# ic.net
KiCad netlist of a schematic drawn in Altium Designer
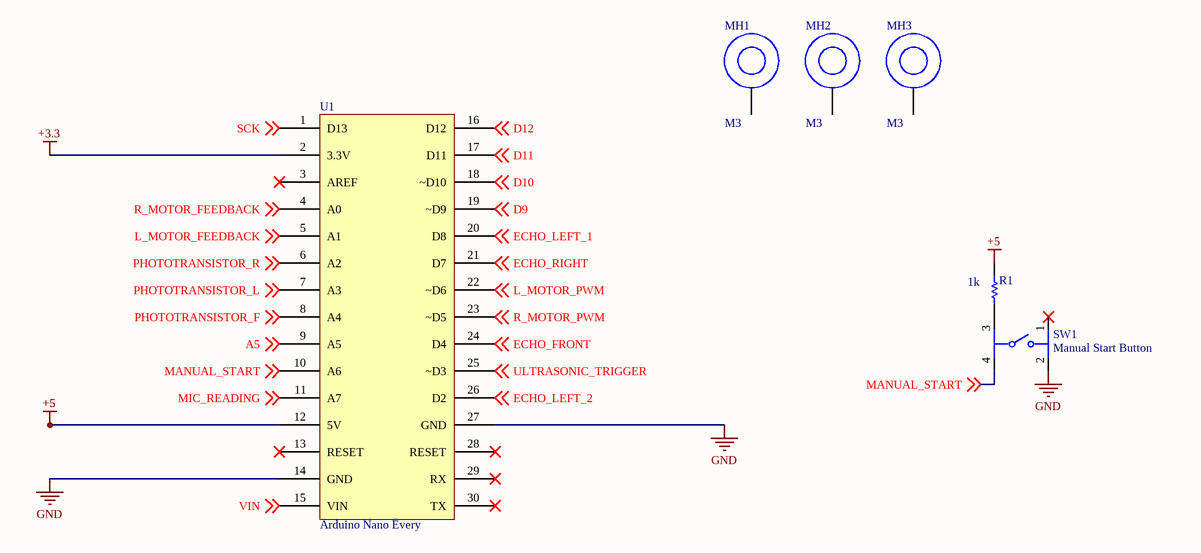
[diagram p0: ic.SchDoc]

(export (version "E")
  (design (tool "Eeschema 10.0.6"))
  (components
    (comp (ref "MH1")
      (value "M3")
      (footprint "PTH_M3")
      (description "M3 Plated Through Hole")
      (libsource (lib "Schlib1") (part "PTH"))
    )
    (comp (ref "MH2")
      (value "M3")
      (footprint "PTH_M3")
      (description "M3 Plated Through Hole")
      (libsource (lib "Schlib1") (part "PTH"))
    )
    (comp (ref "MH3")
      (value "M3")
      (footprint "PTH_M3")
      (description "M3 Plated Through Hole")
      (libsource (lib "Schlib1") (part "PTH"))
    )
    (comp (ref "R1")
      (value "1k")
      (footprint "RESC2013X50X30NL20T20")
      (fields (field (name "PART NUMBER") "CRCW08051K00FKEA") (field (name "MANUFACTURER") "Vishay Dale"))
      (libsource (lib "Altium Content Vault") (part "RES"))
    )
    (comp (ref "SW1")
      (value "Manual Start Button")
      (footprint "FP-PTS645SM43SMTR92LFS-MFG")
      (description "SWITCH TACTILE SPST-NO 0.05A 12V")
      (fields (field (name "MPN") "PTS645SM43SMTR92LFS"))
      (libsource (lib "Altium Content Vault") (part "1adf0dd01260c80cf25a44bfd6b99ba"))
    )
    (comp (ref "U1")
      (value "Arduino Nano Every")
      (footprint "Arduino Nano")
      (libsource (lib "3400 Sch Lib") (part "Arduino Mount"))
    )
  )
  (nets
    (net (code "1") (name "+3.3") (class "Default")
      (node (ref "U1") (pin "2") (pinfunction "3.3V_2") (pintype "passive"))
    )
    (net (code "2") (name "+5") (class "Default")
      (node (ref "R1") (pin "2") (pinfunction "2_2") (pintype "passive"))
      (node (ref "U1") (pin "12") (pinfunction "5V_12") (pintype "passive"))
    )
    (net (code "3") (name "A5") (class "Default")
      (node (ref "U1") (pin "9") (pinfunction "A5_9") (pintype "passive"))
    )
    (net (code "4") (name "D9") (class "Default")
      (node (ref "U1") (pin "19") (pinfunction "~D9_19") (pintype "passive"))
    )
    (net (code "5") (name "D10") (class "Default")
      (node (ref "U1") (pin "18") (pinfunction "~D10_18") (pintype "passive"))
    )
    (net (code "6") (name "D11") (class "Default")
      (node (ref "U1") (pin "17") (pinfunction "D11_17") (pintype "passive"))
    )
    (net (code "7") (name "D12") (class "Default")
      (node (ref "U1") (pin "16") (pinfunction "D12_16") (pintype "passive"))
    )
    (net (code "8") (name "ECHO_FRONT") (class "Default")
      (node (ref "U1") (pin "24") (pinfunction "D4_24") (pintype "passive"))
    )
    (net (code "9") (name "ECHO_LEFT_1") (class "Default")
      (node (ref "U1") (pin "20") (pinfunction "D8_20") (pintype "passive"))
    )
    (net (code "10") (name "ECHO_LEFT_2") (class "Default")
      (node (ref "U1") (pin "26") (pinfunction "D2_26") (pintype "passive"))
    )
    (net (code "11") (name "ECHO_RIGHT") (class "Default")
      (node (ref "U1") (pin "21") (pinfunction "D7_21") (pintype "passive"))
    )
    (net (code "12") (name "GND") (class "Default")
      (node (ref "SW1") (pin "2") (pinfunction "2_2") (pintype "passive"))
      (node (ref "U1") (pin "14") (pinfunction "GND_14") (pintype "passive"))
      (node (ref "U1") (pin "27") (pinfunction "GND_27") (pintype "passive"))
    )
    (net (code "13") (name "L_MOTOR_FEEDBACK") (class "Default")
      (node (ref "U1") (pin "5") (pinfunction "A1_5") (pintype "passive"))
    )
    (net (code "14") (name "L_MOTOR_PWM") (class "Default")
      (node (ref "U1") (pin "22") (pinfunction "~D6_22") (pintype "passive"))
    )
    (net (code "15") (name "MANUAL_START") (class "Default")
      (node (ref "SW1") (pin "4") (pinfunction "4_4") (pintype "passive"))
      (node (ref "U1") (pin "10") (pinfunction "A6_10") (pintype "passive"))
    )
    (net (code "16") (name "MIC_READING") (class "Default")
      (node (ref "U1") (pin "11") (pinfunction "A7_11") (pintype "passive"))
    )
    (net (code "17") (name "Net-(R1-Pad1)") (class "Default")
      (node (ref "R1") (pin "1") (pinfunction "1_1") (pintype "passive"))
      (node (ref "SW1") (pin "3") (pinfunction "3_3") (pintype "passive"))
    )
    (net (code "18") (name "PHOTOTRANSISTOR_F") (class "Default")
      (node (ref "U1") (pin "8") (pinfunction "A4_8") (pintype "passive"))
    )
    (net (code "19") (name "PHOTOTRANSISTOR_L") (class "Default")
      (node (ref "U1") (pin "7") (pinfunction "A3_7") (pintype "passive"))
    )
    (net (code "20") (name "PHOTOTRANSISTOR_R") (class "Default")
      (node (ref "U1") (pin "6") (pinfunction "A2_6") (pintype "passive"))
    )
    (net (code "21") (name "R_MOTOR_FEEDBACK") (class "Default")
      (node (ref "U1") (pin "4") (pinfunction "A0_4") (pintype "passive"))
    )
    (net (code "22") (name "R_MOTOR_PWM") (class "Default")
      (node (ref "U1") (pin "23") (pinfunction "~D5_23") (pintype "passive"))
    )
    (net (code "23") (name "SCK") (class "Default")
      (node (ref "U1") (pin "1") (pinfunction "D13_1") (pintype "passive"))
    )
    (net (code "24") (name "ULTRASONIC_TRIGGER") (class "Default")
      (node (ref "U1") (pin "25") (pinfunction "~D3_25") (pintype "passive"))
    )
    (net (code "25") (name "VIN") (class "Default")
      (node (ref "U1") (pin "15") (pinfunction "VIN_15") (pintype "passive"))
    )
    (net (code "26") (name "unconnected-(MH1-Pad1)") (class "Default")
      (node (ref "MH1") (pin "1") (pinfunction "1_1") (pintype "passive"))
    )
    (net (code "27") (name "unconnected-(MH2-Pad1)") (class "Default")
      (node (ref "MH2") (pin "1") (pinfunction "1_1") (pintype "passive"))
    )
    (net (code "28") (name "unconnected-(MH3-Pad1)") (class "Default")
      (node (ref "MH3") (pin "1") (pinfunction "1_1") (pintype "passive"))
    )
    (net (code "29") (name "unconnected-(SW1-Pad1)") (class "Default")
      (node (ref "SW1") (pin "1") (pinfunction "1_1") (pintype "passive+no_connect"))
    )
    (net (code "30") (name "unconnected-(U1-AREF-Pad3)") (class "Default")
      (node (ref "U1") (pin "3") (pinfunction "AREF_3") (pintype "passive+no_connect"))
    )
    (net (code "31") (name "unconnected-(U1-RESET-Pad13)") (class "Default")
      (node (ref "U1") (pin "13") (pinfunction "RESET_13") (pintype "passive+no_connect"))
    )
    (net (code "32") (name "unconnected-(U1-RESET-Pad28)") (class "Default")
      (node (ref "U1") (pin "28") (pinfunction "RESET_28") (pintype "passive+no_connect"))
    )
    (net (code "33") (name "unconnected-(U1-RX-Pad29)") (class "Default")
      (node (ref "U1") (pin "29") (pinfunction "RX_29") (pintype "passive+no_connect"))
    )
    (net (code "34") (name "unconnected-(U1-TX-Pad30)") (class "Default")
      (node (ref "U1") (pin "30") (pinfunction "TX_30") (pintype "passive+no_connect"))
    )
  )
)
